# ATX_Power_Breakout_v1p4.net
KiCad netlist of a schematic drawn in EAGLE
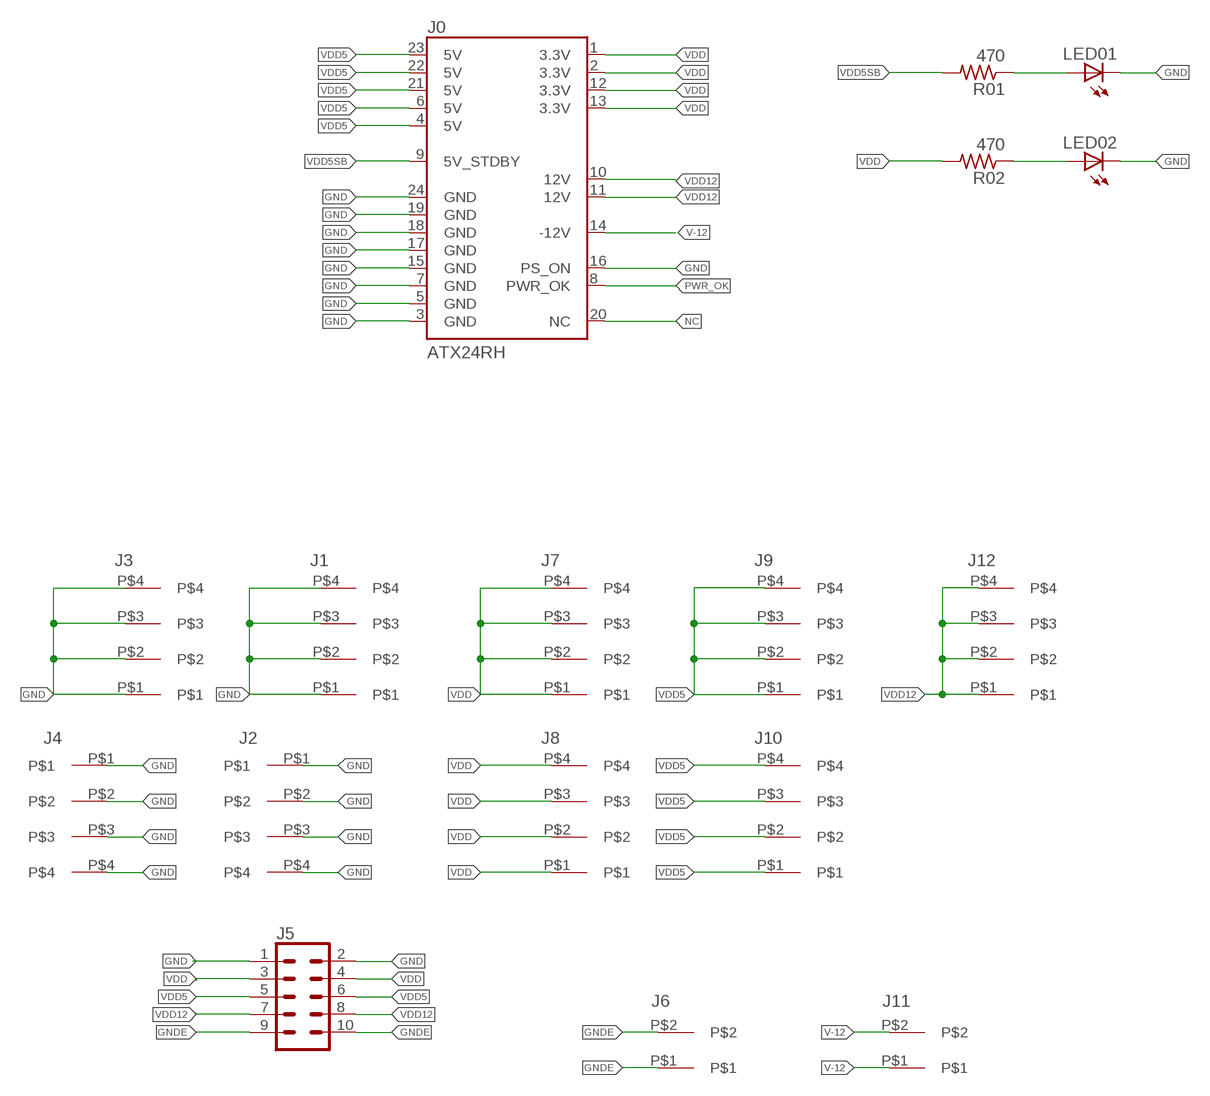
[diagram p0: schematic, sheet 1]

(export (version "E")
  (design (tool "Eeschema 10.0.6"))
  (components
    (comp (ref "J0")
      (value "ATX24RH")
      (footprint "eagle-import:ATX24_RIGHT_ANGLE")
      (libsource (lib "eagle-import") (part "ATX24RH"))
    )
    (comp (ref "J1")
      (value "3.81MM_1_X_4_RT_ANGLE_PLUG_HEADER")
      (footprint "eagle-import:1X4_3.81MM_PITCH")
      (libsource (lib "eagle-import") (part "3.81MM_1_X_4_RT_ANGLE_PLUG_HEADER"))
    )
    (comp (ref "J2")
      (value "3.81MM_1_X_4_RT_ANGLE_PLUG_HEADER")
      (footprint "eagle-import:1X4_3.81MM_PITCH")
      (libsource (lib "eagle-import") (part "3.81MM_1_X_4_RT_ANGLE_PLUG_HEADER"))
    )
    (comp (ref "J3")
      (value "3.81MM_1_X_4_RT_ANGLE_PLUG_HEADER")
      (footprint "eagle-import:1X4_3.81MM_PITCH")
      (libsource (lib "eagle-import") (part "3.81MM_1_X_4_RT_ANGLE_PLUG_HEADER"))
    )
    (comp (ref "J4")
      (value "3.81MM_1_X_4_RT_ANGLE_PLUG_HEADER")
      (footprint "eagle-import:1X4_3.81MM_PITCH")
      (libsource (lib "eagle-import") (part "3.81MM_1_X_4_RT_ANGLE_PLUG_HEADER"))
    )
    (comp (ref "J5")
      (value "CONN_05X2PTH")
      (footprint "eagle-import:2X5")
      (libsource (lib "eagle-import") (part "CONN_05X2PTH"))
    )
    (comp (ref "J6")
      (value "3.81MM_1_X_2_RT_ANGLE_PLUG_HEADER")
      (footprint "eagle-import:2_3.81MM_PITCH")
      (libsource (lib "eagle-import") (part "3.81MM_1_X_2_RT_ANGLE_PLUG_HEADER"))
    )
    (comp (ref "J7")
      (value "3.81MM_1_X_4_RT_ANGLE_PLUG_HEADER")
      (footprint "eagle-import:1X4_3.81MM_PITCH")
      (libsource (lib "eagle-import") (part "3.81MM_1_X_4_RT_ANGLE_PLUG_HEADER"))
    )
    (comp (ref "J8")
      (value "3.81MM_1_X_4_RT_ANGLE_PLUG_HEADER")
      (footprint "eagle-import:1X4_3.81MM_PITCH")
      (libsource (lib "eagle-import") (part "3.81MM_1_X_4_RT_ANGLE_PLUG_HEADER"))
    )
    (comp (ref "J9")
      (value "3.81MM_1_X_4_RT_ANGLE_PLUG_HEADER")
      (footprint "eagle-import:1X4_3.81MM_PITCH")
      (libsource (lib "eagle-import") (part "3.81MM_1_X_4_RT_ANGLE_PLUG_HEADER"))
    )
    (comp (ref "J10")
      (value "3.81MM_1_X_4_RT_ANGLE_PLUG_HEADER")
      (footprint "eagle-import:1X4_3.81MM_PITCH")
      (libsource (lib "eagle-import") (part "3.81MM_1_X_4_RT_ANGLE_PLUG_HEADER"))
    )
    (comp (ref "J11")
      (value "3.81MM_1_X_2_RT_ANGLE_PLUG_HEADER")
      (footprint "eagle-import:2_3.81MM_PITCH")
      (libsource (lib "eagle-import") (part "3.81MM_1_X_2_RT_ANGLE_PLUG_HEADER"))
    )
    (comp (ref "J12")
      (value "3.81MM_1_X_4_RT_ANGLE_PLUG_HEADER")
      (footprint "eagle-import:1X4_3.81MM_PITCH")
      (libsource (lib "eagle-import") (part "3.81MM_1_X_4_RT_ANGLE_PLUG_HEADER"))
    )
    (comp (ref "LED01")
      (value "GREEN")
      (footprint "eagle-import:LED_0805_GREEN")
      (libsource (lib "eagle-import") (part "LED_0805_GREEN"))
    )
    (comp (ref "LED02")
      (value "GREEN")
      (footprint "eagle-import:LED_0805_GREEN")
      (libsource (lib "eagle-import") (part "LED_0805_GREEN"))
    )
    (comp (ref "R01")
      (value "470")
      (footprint "eagle-import:0402")
      (libsource (lib "eagle-import") (part "R_0402"))
    )
    (comp (ref "R02")
      (value "470")
      (footprint "eagle-import:0402")
      (libsource (lib "eagle-import") (part "R_0402"))
    )
  )
  (nets
    (net (code "1") (name "GND") (class "Default")
      (node (ref "J0") (pin "15") (pinfunction "GND_15") (pintype "bidirectional"))
      (node (ref "J0") (pin "16") (pinfunction "PS_ON_16") (pintype "bidirectional"))
      (node (ref "J0") (pin "17") (pinfunction "GND_17") (pintype "bidirectional"))
      (node (ref "J0") (pin "18") (pinfunction "GND_18") (pintype "bidirectional"))
      (node (ref "J0") (pin "19") (pinfunction "GND_19") (pintype "bidirectional"))
      (node (ref "J0") (pin "24") (pinfunction "GND_24") (pintype "bidirectional"))
      (node (ref "J0") (pin "3") (pinfunction "GND_3") (pintype "bidirectional"))
      (node (ref "J0") (pin "5") (pinfunction "GND_5") (pintype "bidirectional"))
      (node (ref "J0") (pin "7") (pinfunction "GND_7") (pintype "bidirectional"))
      (node (ref "J1") (pin "P$1") (pinfunction "P$1_P$1") (pintype "bidirectional"))
      (node (ref "J1") (pin "P$2") (pinfunction "P$2_P$2") (pintype "bidirectional"))
      (node (ref "J1") (pin "P$3") (pinfunction "P$3_P$3") (pintype "bidirectional"))
      (node (ref "J1") (pin "P$4") (pinfunction "P$4_P$4") (pintype "bidirectional"))
      (node (ref "J2") (pin "P$1") (pinfunction "P$1_P$1") (pintype "bidirectional"))
      (node (ref "J2") (pin "P$2") (pinfunction "P$2_P$2") (pintype "bidirectional"))
      (node (ref "J2") (pin "P$3") (pinfunction "P$3_P$3") (pintype "bidirectional"))
      (node (ref "J2") (pin "P$4") (pinfunction "P$4_P$4") (pintype "bidirectional"))
      (node (ref "J3") (pin "P$1") (pinfunction "P$1_P$1") (pintype "bidirectional"))
      (node (ref "J3") (pin "P$2") (pinfunction "P$2_P$2") (pintype "bidirectional"))
      (node (ref "J3") (pin "P$3") (pinfunction "P$3_P$3") (pintype "bidirectional"))
      (node (ref "J3") (pin "P$4") (pinfunction "P$4_P$4") (pintype "bidirectional"))
      (node (ref "J4") (pin "P$1") (pinfunction "P$1_P$1") (pintype "bidirectional"))
      (node (ref "J4") (pin "P$2") (pinfunction "P$2_P$2") (pintype "bidirectional"))
      (node (ref "J4") (pin "P$3") (pinfunction "P$3_P$3") (pintype "bidirectional"))
      (node (ref "J4") (pin "P$4") (pinfunction "P$4_P$4") (pintype "bidirectional"))
      (node (ref "J5") (pin "1") (pinfunction "1_1") (pintype "passive"))
      (node (ref "J5") (pin "2") (pinfunction "2_2") (pintype "passive"))
      (node (ref "LED01") (pin "C") (pinfunction "C_C") (pintype "passive"))
      (node (ref "LED02") (pin "C") (pinfunction "C_C") (pintype "passive"))
    )
    (net (code "2") (name "GNDE") (class "Default")
      (node (ref "J5") (pin "10") (pinfunction "10_10") (pintype "passive"))
      (node (ref "J5") (pin "9") (pinfunction "9_9") (pintype "passive"))
      (node (ref "J6") (pin "P$1") (pinfunction "P$1_P$1") (pintype "bidirectional"))
      (node (ref "J6") (pin "P$2") (pinfunction "P$2_P$2") (pintype "bidirectional"))
    )
    (net (code "3") (name "NC") (class "Default")
      (node (ref "J0") (pin "20") (pinfunction "NC_20") (pintype "bidirectional"))
    )
    (net (code "4") (name "Net-(R01-1)") (class "Default")
      (node (ref "LED01") (pin "A") (pinfunction "A_A") (pintype "passive"))
      (node (ref "R01") (pin "P$1") (pinfunction "1_P$1") (pintype "passive"))
    )
    (net (code "5") (name "Net-(R02-1)") (class "Default")
      (node (ref "LED02") (pin "A") (pinfunction "A_A") (pintype "passive"))
      (node (ref "R02") (pin "P$1") (pinfunction "1_P$1") (pintype "passive"))
    )
    (net (code "6") (name "PWR_OK") (class "Default")
      (node (ref "J0") (pin "8") (pinfunction "PWR_OK_8") (pintype "bidirectional"))
    )
    (net (code "7") (name "V-12") (class "Default")
      (node (ref "J0") (pin "14") (pinfunction "-12V_14") (pintype "bidirectional"))
      (node (ref "J11") (pin "P$1") (pinfunction "P$1_P$1") (pintype "bidirectional"))
      (node (ref "J11") (pin "P$2") (pinfunction "P$2_P$2") (pintype "bidirectional"))
    )
    (net (code "8") (name "VDD") (class "Default")
      (node (ref "J0") (pin "1") (pinfunction "3.3V_1") (pintype "bidirectional"))
      (node (ref "J0") (pin "12") (pinfunction "3.3V_12") (pintype "bidirectional"))
      (node (ref "J0") (pin "13") (pinfunction "3.3V_13") (pintype "bidirectional"))
      (node (ref "J0") (pin "2") (pinfunction "3.3V_2") (pintype "bidirectional"))
      (node (ref "J5") (pin "3") (pinfunction "3_3") (pintype "passive"))
      (node (ref "J5") (pin "4") (pinfunction "4_4") (pintype "passive"))
      (node (ref "J7") (pin "P$1") (pinfunction "P$1_P$1") (pintype "bidirectional"))
      (node (ref "J7") (pin "P$2") (pinfunction "P$2_P$2") (pintype "bidirectional"))
      (node (ref "J7") (pin "P$3") (pinfunction "P$3_P$3") (pintype "bidirectional"))
      (node (ref "J7") (pin "P$4") (pinfunction "P$4_P$4") (pintype "bidirectional"))
      (node (ref "J8") (pin "P$1") (pinfunction "P$1_P$1") (pintype "bidirectional"))
      (node (ref "J8") (pin "P$2") (pinfunction "P$2_P$2") (pintype "bidirectional"))
      (node (ref "J8") (pin "P$3") (pinfunction "P$3_P$3") (pintype "bidirectional"))
      (node (ref "J8") (pin "P$4") (pinfunction "P$4_P$4") (pintype "bidirectional"))
      (node (ref "R02") (pin "P$2") (pinfunction "2_P$2") (pintype "passive"))
    )
    (net (code "9") (name "VDD5") (class "Default")
      (node (ref "J0") (pin "21") (pinfunction "5V_21") (pintype "bidirectional"))
      (node (ref "J0") (pin "22") (pinfunction "5V_22") (pintype "bidirectional"))
      (node (ref "J0") (pin "23") (pinfunction "5V_23") (pintype "bidirectional"))
      (node (ref "J0") (pin "4") (pinfunction "5V_4") (pintype "bidirectional"))
      (node (ref "J0") (pin "6") (pinfunction "5V_6") (pintype "bidirectional"))
      (node (ref "J10") (pin "P$1") (pinfunction "P$1_P$1") (pintype "bidirectional"))
      (node (ref "J10") (pin "P$2") (pinfunction "P$2_P$2") (pintype "bidirectional"))
      (node (ref "J10") (pin "P$3") (pinfunction "P$3_P$3") (pintype "bidirectional"))
      (node (ref "J10") (pin "P$4") (pinfunction "P$4_P$4") (pintype "bidirectional"))
      (node (ref "J5") (pin "5") (pinfunction "5_5") (pintype "passive"))
      (node (ref "J5") (pin "6") (pinfunction "6_6") (pintype "passive"))
      (node (ref "J9") (pin "P$1") (pinfunction "P$1_P$1") (pintype "bidirectional"))
      (node (ref "J9") (pin "P$2") (pinfunction "P$2_P$2") (pintype "bidirectional"))
      (node (ref "J9") (pin "P$3") (pinfunction "P$3_P$3") (pintype "bidirectional"))
      (node (ref "J9") (pin "P$4") (pinfunction "P$4_P$4") (pintype "bidirectional"))
    )
    (net (code "10") (name "VDD5SB") (class "Default")
      (node (ref "J0") (pin "9") (pinfunction "5V_STDBY_9") (pintype "bidirectional"))
      (node (ref "R01") (pin "P$2") (pinfunction "2_P$2") (pintype "passive"))
    )
    (net (code "11") (name "VDD12") (class "Default")
      (node (ref "J0") (pin "10") (pinfunction "12V_10") (pintype "bidirectional"))
      (node (ref "J0") (pin "11") (pinfunction "12V_11") (pintype "bidirectional"))
      (node (ref "J12") (pin "P$1") (pinfunction "P$1_P$1") (pintype "bidirectional"))
      (node (ref "J12") (pin "P$2") (pinfunction "P$2_P$2") (pintype "bidirectional"))
      (node (ref "J12") (pin "P$3") (pinfunction "P$3_P$3") (pintype "bidirectional"))
      (node (ref "J12") (pin "P$4") (pinfunction "P$4_P$4") (pintype "bidirectional"))
      (node (ref "J5") (pin "7") (pinfunction "7_7") (pintype "passive"))
      (node (ref "J5") (pin "8") (pinfunction "8_8") (pintype "passive"))
    )
  )
)
